# ESP_Guage_PCB_Sch.net
KiCad netlist of a schematic drawn in Altium Designer
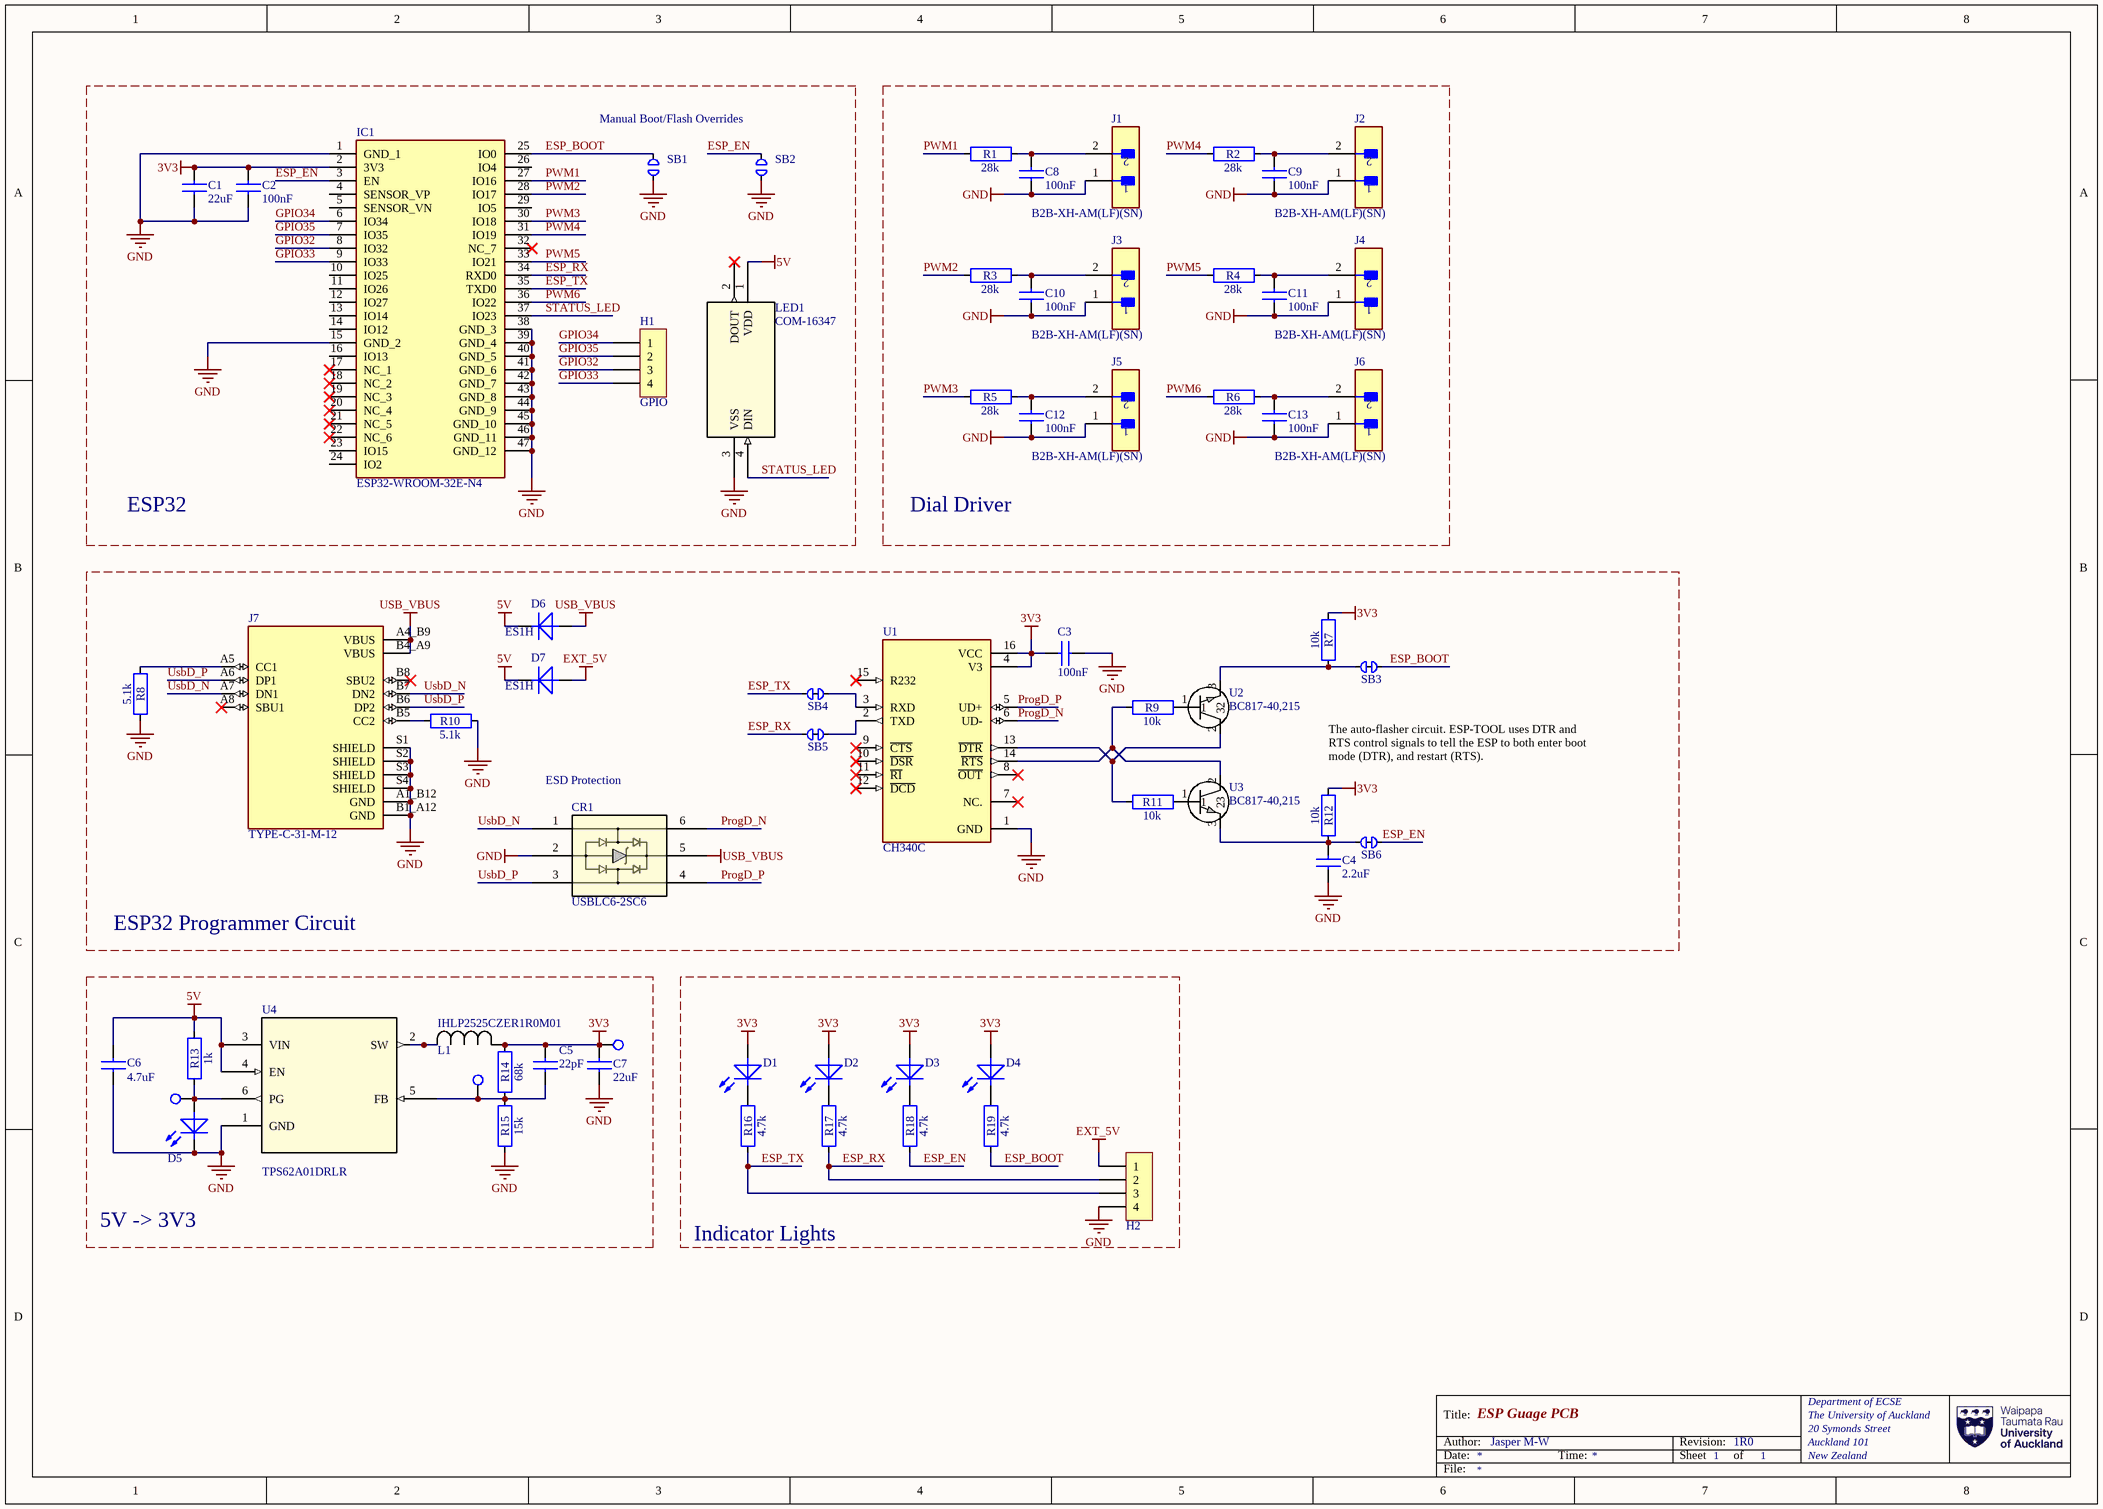
[diagram p0: ESP Guage PCB_Sch.SchDoc]

(export (version "E")
  (design (tool "Eeschema 10.0.6"))
  (components
    (comp (ref "C1")
      (value "22uF")
      (footprint "C0805")
      (description "Generic 0805 cramic capacitor")
      (libsource (lib "UGs@UoA") (part "CCAP0805"))
    )
    (comp (ref "C2")
      (value "100nF")
      (footprint "C0805")
      (description "Generic 0805 cramic capacitor")
      (libsource (lib "UGs@UoA") (part "CCAP0805"))
    )
    (comp (ref "C3")
      (value "100nF")
      (footprint "C0805")
      (description "Generic 0805 cramic capacitor")
      (libsource (lib "UGs@UoA") (part "CCAP0805"))
    )
    (comp (ref "C4")
      (value "2.2uF")
      (footprint "C0805")
      (description "Generic 0805 cramic capacitor")
      (libsource (lib "UGs@UoA") (part "CCAP0805"))
    )
    (comp (ref "C5")
      (value "22pF")
      (footprint "C0805")
      (description "Generic 0805 cramic capacitor")
      (libsource (lib "UGs@UoA") (part "CCAP0805"))
    )
    (comp (ref "C6")
      (value "4.7uF")
      (footprint "C0805")
      (description "Generic 0805 cramic capacitor")
      (libsource (lib "UGs@UoA") (part "CCAP0805"))
    )
    (comp (ref "C7")
      (value "22uF")
      (footprint "C0805")
      (description "Generic 0805 cramic capacitor")
      (libsource (lib "UGs@UoA") (part "CCAP0805"))
    )
    (comp (ref "C8")
      (value "100nF")
      (footprint "C0805")
      (description "Generic 0805 cramic capacitor")
      (libsource (lib "UGs@UoA") (part "CCAP0805"))
    )
    (comp (ref "C9")
      (value "100nF")
      (footprint "C0805")
      (description "Generic 0805 cramic capacitor")
      (libsource (lib "UGs@UoA") (part "CCAP0805"))
    )
    (comp (ref "C10")
      (value "100nF")
      (footprint "C0805")
      (description "Generic 0805 cramic capacitor")
      (libsource (lib "UGs@UoA") (part "CCAP0805"))
    )
    (comp (ref "C11")
      (value "100nF")
      (footprint "C0805")
      (description "Generic 0805 cramic capacitor")
      (libsource (lib "UGs@UoA") (part "CCAP0805"))
    )
    (comp (ref "C12")
      (value "100nF")
      (footprint "C0805")
      (description "Generic 0805 cramic capacitor")
      (libsource (lib "UGs@UoA") (part "CCAP0805"))
    )
    (comp (ref "C13")
      (value "100nF")
      (footprint "C0805")
      (description "Generic 0805 cramic capacitor")
      (libsource (lib "UGs@UoA") (part "CCAP0805"))
    )
    (comp (ref "CR1")
      (value "USBLC6-2SC6")
      (footprint "SOT23-6L_STM")
      (description "ESD Protection for USB 2.0 High Speed")
      (fields (field (name "COPYRIGHT") "Copyright (C) 2025 Ultra Librarian. All rights reserved."))
      (libsource (lib "ESDProtect_USBLC6-2SC6") (part "USBLC6-2SC6"))
    )
    (comp (ref "D1")
      (value "LED_0805")
      (footprint "LED_0805-Footprint-1")
      (description "Generic SMT LED 0805")
      (libsource (lib "UGs@UoA") (part "LED"))
    )
    (comp (ref "D2")
      (value "LED_0805")
      (footprint "LED_0805-Footprint-1")
      (description "Generic SMT LED 0805")
      (libsource (lib "UGs@UoA") (part "LED"))
    )
    (comp (ref "D3")
      (value "LED_0805")
      (footprint "LED_0805-Footprint-1")
      (description "Generic SMT LED 0805")
      (libsource (lib "UGs@UoA") (part "LED"))
    )
    (comp (ref "D4")
      (value "LED_0805")
      (footprint "LED_0805-Footprint-1")
      (description "Generic SMT LED 0805")
      (libsource (lib "UGs@UoA") (part "LED"))
    )
    (comp (ref "D5")
      (value "LED_0805")
      (footprint "LED_0805-Footprint-1")
      (description "Generic SMT LED 0805")
      (libsource (lib "UGs@UoA") (part "LED"))
    )
    (comp (ref "D6")
      (value "ES1H")
      (footprint "DO-214AC")
      (description "Rectifier Diode, 1 Phase, 1 Element, 1A, 500V V(RRM), Silicon, DO-214AC")
      (libsource (lib "UGs@UoA") (part "Diode"))
    )
    (comp (ref "D7")
      (value "ES1H")
      (footprint "DO-214AC")
      (description "Rectifier Diode, 1 Phase, 1 Element, 1A, 500V V(RRM), Silicon, DO-214AC")
      (libsource (lib "UGs@UoA") (part "Diode"))
    )
    (comp (ref "H1")
      (value "GPIO")
      (footprint "HEADER_2.54MM_1x4PIN")
      (description "JTAG")
      (libsource (lib "Generic") (part "1x4 Header 2.54mm"))
    )
    (comp (ref "H2")
      (value "1x4 Header 2.54mm")
      (footprint "HEADER_2.54MM_1x4PIN")
      (libsource (lib "Generic") (part "1x4 Header 2.54mm"))
    )
    (comp (ref "IC1")
      (value "ESP32-WROOM-32E-N4")
      (footprint "ESP32WROOM32EN4")
      (description "RX TXRX MOD WIFI TRACE ANT SMD")
      (fields (field (name "MOUSER PART NUMBER") "356-ESP32WRM32E132PH"))
      (libsource (lib "ESP32-WROOM-32E-N4") (part "ESP32-WROOM-32E-N4"))
    )
    (comp (ref "J1")
      (value "B2B-XH-AM(LF)(SN)")
      (footprint "FP-B2B-XH-AM_LF_SN-MFG")
      (description "CONN HEADER VERT 2POS 2.5MM")
      (libsource (lib "Altium Content Vault") (part "3bc925449376181038e59eaffc5286c"))
    )
    (comp (ref "J2")
      (value "B2B-XH-AM(LF)(SN)")
      (footprint "FP-B2B-XH-AM_LF_SN-MFG")
      (description "CONN HEADER VERT 2POS 2.5MM")
      (libsource (lib "Altium Content Vault") (part "3bc925449376181038e59eaffc5286c"))
    )
    (comp (ref "J3")
      (value "B2B-XH-AM(LF)(SN)")
      (footprint "FP-B2B-XH-AM_LF_SN-MFG")
      (description "CONN HEADER VERT 2POS 2.5MM")
      (libsource (lib "Altium Content Vault") (part "3bc925449376181038e59eaffc5286c"))
    )
    (comp (ref "J4")
      (value "B2B-XH-AM(LF)(SN)")
      (footprint "FP-B2B-XH-AM_LF_SN-MFG")
      (description "CONN HEADER VERT 2POS 2.5MM")
      (libsource (lib "Altium Content Vault") (part "3bc925449376181038e59eaffc5286c"))
    )
    (comp (ref "J5")
      (value "B2B-XH-AM(LF)(SN)")
      (footprint "FP-B2B-XH-AM_LF_SN-MFG")
      (description "CONN HEADER VERT 2POS 2.5MM")
      (libsource (lib "Altium Content Vault") (part "3bc925449376181038e59eaffc5286c"))
    )
    (comp (ref "J6")
      (value "B2B-XH-AM(LF)(SN)")
      (footprint "FP-B2B-XH-AM_LF_SN-MFG")
      (description "CONN HEADER VERT 2POS 2.5MM")
      (libsource (lib "Altium Content Vault") (part "3bc925449376181038e59eaffc5286c"))
    )
    (comp (ref "J7")
      (value "TYPE-C-31-M-12")
      (footprint "HRO_TYPE-C-31-M-12")
      (description "USB Connectors 24 Receptacle 1 8.94*7.3mm RoHS")
      (fields (field (name "MF") "HRO Electronics Co., Ltd."))
      (libsource (lib "UsbFull_TYPE-C-31-M-12") (part "TYPE-C-31-M-12"))
    )
    (comp (ref "L1")
      (value "IHLP2525CZER1R0M01")
      (footprint "IND_IHLP-2525CZ-01_VIS")
      (description "IHLP-2525CZ-01 1 20% ER E3 1uH")
      (fields (field (name "COPYRIGHT") "Copyright (C) 2025 Ultra Librarian. All rights reserved."))
      (libsource (lib "PowerIndcutor_IHLP2525CZER1R0M01") (part "IHLP2525CZER1R0M01"))
    )
    (comp (ref "LED1")
      (value "COM-16347")
      (footprint "COM-16347_SPK")
      (description "Description")
      (fields (field (name "COPYRIGHT") "Copyright (C) 2026 Ultra Librarian. All rights reserved."))
      (libsource (lib "AddrLED_COM-16347") (part "COM-16347"))
    )
    (comp (ref "R1")
      (value "28k")
      (footprint "R0805")
      (description "Generic 0805 resistor")
      (fields (field (name "Comment") "10kj"))
      (libsource (lib "UGs@UoA") (part "RES0805"))
    )
    (comp (ref "R2")
      (value "28k")
      (footprint "R0805")
      (description "Generic 0805 resistor")
      (fields (field (name "Comment") "10kj"))
      (libsource (lib "UGs@UoA") (part "RES0805"))
    )
    (comp (ref "R3")
      (value "28k")
      (footprint "R0805")
      (description "Generic 0805 resistor")
      (fields (field (name "Comment") "10kj"))
      (libsource (lib "UGs@UoA") (part "RES0805"))
    )
    (comp (ref "R4")
      (value "28k")
      (footprint "R0805")
      (description "Generic 0805 resistor")
      (fields (field (name "Comment") "10kj"))
      (libsource (lib "UGs@UoA") (part "RES0805"))
    )
    (comp (ref "R5")
      (value "28k")
      (footprint "R0805")
      (description "Generic 0805 resistor")
      (fields (field (name "Comment") "10kj"))
      (libsource (lib "UGs@UoA") (part "RES0805"))
    )
    (comp (ref "R6")
      (value "28k")
      (footprint "R0805")
      (description "Generic 0805 resistor")
      (fields (field (name "Comment") "10kj"))
      (libsource (lib "UGs@UoA") (part "RES0805"))
    )
    (comp (ref "R7")
      (value "10k")
      (footprint "R0805")
      (description "Generic 0805 resistor")
      (fields (field (name "Comment") "10kj"))
      (libsource (lib "") (part "RES0805_1"))
    )
    (comp (ref "R8")
      (value "5.1k")
      (footprint "R0805")
      (description "Generic 0805 resistor")
      (fields (field (name "Comment") "10kj"))
      (libsource (lib "") (part "RES0805_1"))
    )
    (comp (ref "R9")
      (value "10k")
      (footprint "R0805")
      (description "Generic 0805 resistor")
      (fields (field (name "Comment") "10kj"))
      (libsource (lib "UGs@UoA") (part "RES0805"))
    )
    (comp (ref "R10")
      (value "5.1k")
      (footprint "R0805")
      (description "Generic 0805 resistor")
      (fields (field (name "Comment") "10kj"))
      (libsource (lib "UGs@UoA") (part "RES0805"))
    )
    (comp (ref "R11")
      (value "10k")
      (footprint "R0805")
      (description "Generic 0805 resistor")
      (fields (field (name "Comment") "10kj"))
      (libsource (lib "UGs@UoA") (part "RES0805"))
    )
    (comp (ref "R12")
      (value "10k")
      (footprint "R0805")
      (description "Generic 0805 resistor")
      (fields (field (name "Comment") "10kj"))
      (libsource (lib "") (part "RES0805_1"))
    )
    (comp (ref "R13")
      (value "1k")
      (footprint "R0805")
      (description "Generic 0805 resistor")
      (fields (field (name "Comment") "10kj"))
      (libsource (lib "") (part "RES0805_2"))
    )
    (comp (ref "R14")
      (value "68k")
      (footprint "R0805")
      (description "Generic 0805 resistor")
      (fields (field (name "Comment") "10kj"))
      (libsource (lib "") (part "RES0805_2"))
    )
    (comp (ref "R15")
      (value "15k")
      (footprint "R0805")
      (description "Generic 0805 resistor")
      (fields (field (name "Comment") "10kj"))
      (libsource (lib "") (part "RES0805_2"))
    )
    (comp (ref "R16")
      (value "4.7k")
      (footprint "R0805")
      (description "Generic 0805 resistor")
      (fields (field (name "Comment") "10kj"))
      (libsource (lib "") (part "RES0805_2"))
    )
    (comp (ref "R17")
      (value "4.7k")
      (footprint "R0805")
      (description "Generic 0805 resistor")
      (fields (field (name "Comment") "10kj"))
      (libsource (lib "") (part "RES0805_2"))
    )
    (comp (ref "R18")
      (value "4.7k")
      (footprint "R0805")
      (description "Generic 0805 resistor")
      (fields (field (name "Comment") "10kj"))
      (libsource (lib "") (part "RES0805_2"))
    )
    (comp (ref "R19")
      (value "4.7k")
      (footprint "R0805")
      (description "Generic 0805 resistor")
      (fields (field (name "Comment") "10kj"))
      (libsource (lib "") (part "RES0805_2"))
    )
    (comp (ref "SB1")
      (value "Solder Jumper Normally Open 0201")
      (footprint "Solder Bridge Open 0201")
      (libsource (lib "Generic") (part "Solder Jumper Normally Open 0201"))
    )
    (comp (ref "SB2")
      (value "Solder Jumper Normally Open 0201")
      (footprint "Solder Bridge Open 0201")
      (libsource (lib "Generic") (part "Solder Jumper Normally Open 0201"))
    )
    (comp (ref "SB3")
      (value "Solder Jumper Normally Closed 0201")
      (footprint "Solder Bridge Closed 0201")
      (libsource (lib "Generic") (part "Solder Jumper Normally Closed 0201"))
    )
    (comp (ref "SB4")
      (value "Solder Jumper Normally Closed 0201")
      (footprint "Solder Bridge Closed 0201")
      (libsource (lib "Generic") (part "Solder Jumper Normally Closed 0201"))
    )
    (comp (ref "SB5")
      (value "Solder Jumper Normally Closed 0201")
      (footprint "Solder Bridge Closed 0201")
      (libsource (lib "Generic") (part "Solder Jumper Normally Closed 0201"))
    )
    (comp (ref "SB6")
      (value "Solder Jumper Normally Closed 0201")
      (footprint "Solder Bridge Closed 0201")
      (libsource (lib "Generic") (part "Solder Jumper Normally Closed 0201"))
    )
    (comp (ref "T_5")
      (value "Surface Test Pad")
      (footprint "Test Pad")
      (libsource (lib "Generic") (part "Surface Test Pad"))
    )
    (comp (ref "T_FB1")
      (value "Surface Test Pad")
      (footprint "Test Pad")
      (libsource (lib "Generic") (part "Surface Test Pad"))
    )
    (comp (ref "T_PROG1")
      (value "Surface Test Pad")
      (footprint "Test Pad")
      (libsource (lib "Generic") (part "Surface Test Pad"))
    )
    (comp (ref "U1")
      (value "CH340C")
      (footprint "SOIC127P600X180-16N")
      (description "USB to serial chip CH340")
      (fields (field (name "MF") "WCH"))
      (libsource (lib "CH340C") (part "CH340C"))
    )
    (comp (ref "U2")
      (value "BC817-40,215")
      (footprint "SOT23_NEX")
      (description "Description")
      (fields (field (name "COPYRIGHT") "Copyright (C) 2026 Ultra Librarian. All rights reserved."))
      (libsource (lib "NPNTransistor_BC817-40,215") (part "BC817-40,215"))
    )
    (comp (ref "U3")
      (value "BC817-40,215")
      (footprint "SOT23_NEX")
      (description "Description")
      (fields (field (name "COPYRIGHT") "Copyright (C) 2026 Ultra Librarian. All rights reserved."))
      (libsource (lib "NPNTransistor_BC817-40,215") (part "BC817-40,215"))
    )
    (comp (ref "U4")
      (value "TPS62A01DRLR")
      (footprint "SOT6_DRL_TEX")
      (description "2.5V-to-5.5V input, 1A output high-efficiency step-down converter 6-SOT-5X3 -40 to 125")
      (fields (field (name "COPYRIGHT") "Copyright (C) 2025 Ultra Librarian. All rights reserved."))
      (libsource (lib "BuckReg_TPS62A01DRLR") (part "TPS62A01DRLR"))
    )
  )
  (nets
    (net (code "1") (name "/ESP_BOOT") (class "Default")
      (node (ref "IC1") (pin "25") (pinfunction "IO0_25") (pintype "passive"))
      (node (ref "R19") (pin "1") (pinfunction "1_1") (pintype "passive"))
      (node (ref "SB1") (pin "2") (pinfunction "2_2") (pintype "passive"))
      (node (ref "SB3") (pin "1") (pinfunction "1_1") (pintype "passive"))
    )
    (net (code "2") (name "/ESP_EN") (class "Default")
      (node (ref "IC1") (pin "3") (pinfunction "EN_3") (pintype "passive"))
      (node (ref "R18") (pin "1") (pinfunction "1_1") (pintype "passive"))
      (node (ref "SB2") (pin "2") (pinfunction "2_2") (pintype "passive"))
      (node (ref "SB6") (pin "1") (pinfunction "1_1") (pintype "passive"))
    )
    (net (code "3") (name "/ESP_RX") (class "Default")
      (node (ref "H2") (pin "2") (pinfunction "2_2") (pintype "passive"))
      (node (ref "IC1") (pin "34") (pinfunction "RXD0_34") (pintype "passive"))
      (node (ref "R17") (pin "1") (pinfunction "1_1") (pintype "passive"))
      (node (ref "SB5") (pin "2") (pinfunction "2_2") (pintype "passive"))
    )
    (net (code "4") (name "/ESP_TX") (class "Default")
      (node (ref "H2") (pin "3") (pinfunction "3_3") (pintype "passive"))
      (node (ref "IC1") (pin "35") (pinfunction "TXD0_35") (pintype "passive"))
      (node (ref "R16") (pin "1") (pinfunction "1_1") (pintype "passive"))
      (node (ref "SB4") (pin "2") (pinfunction "2_2") (pintype "passive"))
    )
    (net (code "5") (name "/GPIO32") (class "Default")
      (node (ref "H1") (pin "3") (pinfunction "3_3") (pintype "passive"))
      (node (ref "IC1") (pin "8") (pinfunction "IO32_8") (pintype "passive"))
    )
    (net (code "6") (name "/GPIO33") (class "Default")
      (node (ref "H1") (pin "4") (pinfunction "4_4") (pintype "passive"))
      (node (ref "IC1") (pin "9") (pinfunction "IO33_9") (pintype "passive"))
    )
    (net (code "7") (name "/GPIO34") (class "Default")
      (node (ref "H1") (pin "1") (pinfunction "1_1") (pintype "passive"))
      (node (ref "IC1") (pin "6") (pinfunction "IO34_6") (pintype "passive"))
    )
    (net (code "8") (name "/GPIO35") (class "Default")
      (node (ref "H1") (pin "2") (pinfunction "2_2") (pintype "passive"))
      (node (ref "IC1") (pin "7") (pinfunction "IO35_7") (pintype "passive"))
    )
    (net (code "9") (name "/PWM1") (class "Default")
      (node (ref "IC1") (pin "27") (pinfunction "IO16_27") (pintype "passive"))
      (node (ref "R1") (pin "1") (pinfunction "1_1") (pintype "passive"))
    )
    (net (code "10") (name "/PWM2") (class "Default")
      (node (ref "IC1") (pin "28") (pinfunction "IO17_28") (pintype "passive"))
      (node (ref "R3") (pin "1") (pinfunction "1_1") (pintype "passive"))
    )
    (net (code "11") (name "/PWM3") (class "Default")
      (node (ref "IC1") (pin "30") (pinfunction "IO18_30") (pintype "passive"))
      (node (ref "R5") (pin "1") (pinfunction "1_1") (pintype "passive"))
    )
    (net (code "12") (name "/PWM4") (class "Default")
      (node (ref "IC1") (pin "31") (pinfunction "IO19_31") (pintype "passive"))
      (node (ref "R2") (pin "1") (pinfunction "1_1") (pintype "passive"))
    )
    (net (code "13") (name "/PWM5") (class "Default")
      (node (ref "IC1") (pin "33") (pinfunction "IO21_33") (pintype "passive"))
      (node (ref "R4") (pin "1") (pinfunction "1_1") (pintype "passive"))
    )
    (net (code "14") (name "/PWM6") (class "Default")
      (node (ref "IC1") (pin "36") (pinfunction "IO22_36") (pintype "passive"))
      (node (ref "R6") (pin "1") (pinfunction "1_1") (pintype "passive"))
    )
    (net (code "15") (name "/ProgD_N") (class "Default")
      (node (ref "CR1") (pin "6") (pinfunction "6_6") (pintype "passive"))
      (node (ref "U1") (pin "6") (pinfunction "UD-_6") (pintype "bidirectional"))
    )
    (net (code "16") (name "/ProgD_P") (class "Default")
      (node (ref "CR1") (pin "4") (pinfunction "4_4") (pintype "passive"))
      (node (ref "U1") (pin "5") (pinfunction "UD+_5") (pintype "bidirectional"))
    )
    (net (code "17") (name "/STATUS_LED") (class "Default")
      (node (ref "IC1") (pin "37") (pinfunction "IO23_37") (pintype "passive"))
      (node (ref "LED1") (pin "4") (pinfunction "DIN_4") (pintype "input"))
    )
    (net (code "18") (name "/UsbD_N") (class "Default")
      (node (ref "CR1") (pin "1") (pinfunction "1_1") (pintype "passive"))
      (node (ref "J7") (pin "A7") (pinfunction "DN1_A7") (pintype "bidirectional"))
      (node (ref "J7") (pin "B7") (pinfunction "DN2_B7") (pintype "bidirectional"))
    )
    (net (code "19") (name "/UsbD_P") (class "Default")
      (node (ref "CR1") (pin "3") (pinfunction "3_3") (pintype "passive"))
      (node (ref "J7") (pin "A6") (pinfunction "DP1_A6") (pintype "bidirectional"))
      (node (ref "J7") (pin "B6") (pinfunction "DP2_B6") (pintype "bidirectional"))
    )
    (net (code "20") (name "3V3") (class "Default")
      (node (ref "C1") (pin "2") (pinfunction "2_2") (pintype "passive"))
      (node (ref "C2") (pin "2") (pinfunction "2_2") (pintype "passive"))
      (node (ref "C3") (pin "2") (pinfunction "2_2") (pintype "passive"))
      (node (ref "C5") (pin "2") (pinfunction "2_2") (pintype "passive"))
      (node (ref "C7") (pin "2") (pinfunction "2_2") (pintype "passive"))
      (node (ref "D1") (pin "2") (pinfunction "A_2") (pintype "passive"))
      (node (ref "D2") (pin "2") (pinfunction "A_2") (pintype "passive"))
      (node (ref "D3") (pin "2") (pinfunction "A_2") (pintype "passive"))
      (node (ref "D4") (pin "2") (pinfunction "A_2") (pintype "passive"))
      (node (ref "IC1") (pin "2") (pinfunction "3V3_2") (pintype "passive"))
      (node (ref "L1") (pin "2") (pinfunction "2_2") (pintype "passive"))
      (node (ref "R12") (pin "1") (pinfunction "1_1") (pintype "passive"))
      (node (ref "R14") (pin "2") (pinfunction "2_2") (pintype "passive"))
      (node (ref "R7") (pin "1") (pinfunction "1_1") (pintype "passive"))
      (node (ref "T_5") (pin "1") (pinfunction "0_1") (pintype "passive"))
      (node (ref "U1") (pin "16") (pinfunction "VCC_16") (pintype "power_in"))
      (node (ref "U1") (pin "4") (pinfunction "V3_4") (pintype "power_in"))
    )
    (net (code "21") (name "5V") (class "Default")
      (node (ref "C6") (pin "2") (pinfunction "2_2") (pintype "passive"))
      (node (ref "D6") (pin "1") (pinfunction "K_1") (pintype "passive"))
      (node (ref "D7") (pin "1") (pinfunction "K_1") (pintype "passive"))
      (node (ref "LED1") (pin "1") (pinfunction "VDD_1") (pintype "power_in"))
      (node (ref "R13") (pin "2") (pinfunction "2_2") (pintype "passive"))
      (node (ref "U4") (pin "3") (pinfunction "VIN_3") (pintype "power_in"))
      (node (ref "U4") (pin "4") (pinfunction "EN_4") (pintype "input"))
    )
    (net (code "22") (name "EXT_5V") (class "Default")
      (node (ref "D7") (pin "2") (pinfunction "A_2") (pintype "passive"))
      (node (ref "H2") (pin "1") (pinfunction "1_1") (pintype "passive"))
    )
    (net (code "23") (name "GND") (class "Default")
      (node (ref "C1") (pin "1") (pinfunction "1_1") (pintype "passive"))
      (node (ref "C10") (pin "2") (pinfunction "2_2") (pintype "passive"))
      (node (ref "C11") (pin "2") (pinfunction "2_2") (pintype "passive"))
      (node (ref "C12") (pin "2") (pinfunction "2_2") (pintype "passive"))
      (node (ref "C13") (pin "2") (pinfunction "2_2") (pintype "passive"))
      (node (ref "C2") (pin "1") (pinfunction "1_1") (pintype "passive"))
      (node (ref "C3") (pin "1") (pinfunction "1_1") (pintype "passive"))
      (node (ref "C4") (pin "1") (pinfunction "1_1") (pintype "passive"))
      (node (ref "C6") (pin "1") (pinfunction "1_1") (pintype "passive"))
      (node (ref "C7") (pin "1") (pinfunction "1_1") (pintype "passive"))
      (node (ref "C8") (pin "2") (pinfunction "2_2") (pintype "passive"))
      (node (ref "C9") (pin "2") (pinfunction "2_2") (pintype "passive"))
      (node (ref "CR1") (pin "2") (pinfunction "2_2") (pintype "passive"))
      (node (ref "D5") (pin "1") (pinfunction "K_1") (pintype "passive"))
      (node (ref "H2") (pin "4") (pinfunction "4_4") (pintype "passive"))
      (node (ref "IC1") (pin "1") (pinfunction "GND_1_1") (pintype "passive"))
      (node (ref "IC1") (pin "15") (pinfunction "GND_2_15") (pintype "passive"))
      (node (ref "IC1") (pin "38") (pinfunction "GND_3_38") (pintype "passive"))
      (node (ref "IC1") (pin "39") (pinfunction "GND_4_39") (pintype "passive"))
      (node (ref "IC1") (pin "40") (pinfunction "GND_5_40") (pintype "passive"))
      (node (ref "IC1") (pin "41") (pinfunction "GND_6_41") (pintype "passive"))
      (node (ref "IC1") (pin "42") (pinfunction "GND_7_42") (pintype "passive"))
      (node (ref "IC1") (pin "43") (pinfunction "GND_8_43") (pintype "passive"))
      (node (ref "IC1") (pin "44") (pinfunction "GND_9_44") (pintype "passive"))
      (node (ref "IC1") (pin "45") (pinfunction "GND_10_45") (pintype "passive"))
      (node (ref "IC1") (pin "46") (pinfunction "GND_11_46") (pintype "passive"))
      (node (ref "IC1") (pin "47") (pinfunction "GND_12_47") (pintype "passive"))
      (node (ref "J1") (pin "1") (pinfunction "1_1") (pintype "passive"))
      (node (ref "J2") (pin "1") (pinfunction "1_1") (pintype "passive"))
      (node (ref "J3") (pin "1") (pinfunction "1_1") (pintype "passive"))
      (node (ref "J4") (pin "1") (pinfunction "1_1") (pintype "passive"))
      (node (ref "J5") (pin "1") (pinfunction "1_1") (pintype "passive"))
      (node (ref "J6") (pin "1") (pinfunction "1_1") (pintype "passive"))
      (node (ref "J7") (pin "A1_B12") (pinfunction "GND_A1_B12") (pintype "power_in"))
      (node (ref "J7") (pin "B1_A12") (pinfunction "GND_B1_A12") (pintype "power_in"))
      (node (ref "J7") (pin "S1") (pinfunction "SHIELD_S1") (pintype "passive"))
      (node (ref "J7") (pin "S2") (pinfunction "SHIELD_S2") (pintype "passive"))
      (node (ref "J7") (pin "S3") (pinfunction "SHIELD_S3") (pintype "passive"))
      (node (ref "J7") (pin "S4") (pinfunction "SHIELD_S4") (pintype "passive"))
      (node (ref "LED1") (pin "3") (pinfunction "VSS_3") (pintype "power_in"))
      (node (ref "R10") (pin "2") (pinfunction "2_2") (pintype "passive"))
      (node (ref "R15") (pin "1") (pinfunction "1_1") (pintype "passive"))
      (node (ref "R8") (pin "2") (pinfunction "2_2") (pintype "passive"))
      (node (ref "SB1") (pin "1") (pinfunction "1_1") (pintype "passive"))
      (node (ref "SB2") (pin "1") (pinfunction "1_1") (pintype "passive"))
      (node (ref "U1") (pin "1") (pinfunction "GND_1") (pintype "power_in"))
      (node (ref "U4") (pin "1") (pinfunction "GND_1") (pintype "power_in"))
    )
    (net (code "24") (name "Net-(C8-Pad1)") (class "Default")
      (node (ref "C8") (pin "1") (pinfunction "1_1") (pintype "passive"))
      (node (ref "J1") (pin "2") (pinfunction "2_2") (pintype "passive"))
      (node (ref "R1") (pin "2") (pinfunction "2_2") (pintype "passive"))
    )
    (net (code "25") (name "Net-(C9-Pad1)") (class "Default")
      (node (ref "C9") (pin "1") (pinfunction "1_1") (pintype "passive"))
      (node (ref "J2") (pin "2") (pinfunction "2_2") (pintype "passive"))
      (node (ref "R2") (pin "2") (pinfunction "2_2") (pintype "passive"))
    )
    (net (code "26") (name "Net-(C10-Pad1)") (class "Default")
      (node (ref "C10") (pin "1") (pinfunction "1_1") (pintype "passive"))
      (node (ref "J3") (pin "2") (pinfunction "2_2") (pintype "passive"))
      (node (ref "R3") (pin "2") (pinfunction "2_2") (pintype "passive"))
    )
    (net (code "27") (name "Net-(C11-Pad1)") (class "Default")
      (node (ref "C11") (pin "1") (pinfunction "1_1") (pintype "passive"))
      (node (ref "J4") (pin "2") (pinfunction "2_2") (pintype "passive"))
      (node (ref "R4") (pin "2") (pinfunction "2_2") (pintype "passive"))
    )
    (net (code "28") (name "Net-(C12-Pad1)") (class "Default")
      (node (ref "C12") (pin "1") (pinfunction "1_1") (pintype "passive"))
      (node (ref "J5") (pin "2") (pinfunction "2_2") (pintype "passive"))
      (node (ref "R5") (pin "2") (pinfunction "2_2") (pintype "passive"))
    )
    (net (code "29") (name "Net-(C13-Pad1)") (class "Default")
      (node (ref "C13") (pin "1") (pinfunction "1_1") (pintype "passive"))
      (node (ref "J6") (pin "2") (pinfunction "2_2") (pintype "passive"))
      (node (ref "R6") (pin "2") (pinfunction "2_2") (pintype "passive"))
    )
    (net (code "30") (name "Net-(D1-K)") (class "Default")
      (node (ref "D1") (pin "1") (pinfunction "K_1") (pintype "passive"))
      (node (ref "R16") (pin "2") (pinfunction "2_2") (pintype "passive"))
    )
    (net (code "31") (name "Net-(D2-K)") (class "Default")
      (node (ref "D2") (pin "1") (pinfunction "K_1") (pintype "passive"))
      (node (ref "R17") (pin "2") (pinfunction "2_2") (pintype "passive"))
    )
    (net (code "32") (name "Net-(D3-K)") (class "Default")
      (node (ref "D3") (pin "1") (pinfunction "K_1") (pintype "passive"))
      (node (ref "R18") (pin "2") (pinfunction "2_2") (pintype "passive"))
    )
    (net (code "33") (name "Net-(D4-K)") (class "Default")
      (node (ref "D4") (pin "1") (pinfunction "K_1") (pintype "passive"))
      (node (ref "R19") (pin "2") (pinfunction "2_2") (pintype "passive"))
    )
    (net (code "34") (name "Net-(D5-A)") (class "Default")
      (node (ref "D5") (pin "2") (pinfunction "A_2") (pintype "passive"))
      (node (ref "R13") (pin "1") (pinfunction "1_1") (pintype "passive"))
      (node (ref "T_PROG1") (pin "1") (pinfunction "0_1") (pintype "passive"))
      (node (ref "U4") (pin "6") (pinfunction "PG_6") (pintype "output"))
    )
    (net (code "35") (name "Net-(J7-CC1)") (class "Default")
      (node (ref "J7") (pin "A5") (pinfunction "CC1_A5") (pintype "bidirectional"))
      (node (ref "R8") (pin "1") (pinfunction "1_1") (pintype "passive"))
    )
    (net (code "36") (name "Net-(J7-CC2)") (class "Default")
      (node (ref "J7") (pin "B5") (pinfunction "CC2_B5") (pintype "bidirectional"))
      (node (ref "R10") (pin "1") (pinfunction "1_1") (pintype "passive"))
    )
    (net (code "37") (name "Net-(R9-Pad2)") (class "Default")
      (node (ref "R9") (pin "2") (pinfunction "2_2") (pintype "passive"))
      (node (ref "U2") (pin "1") (pinfunction "1_1") (pintype "passive"))
    )
    (net (code "38") (name "Net-(R11-Pad2)") (class "Default")
      (node (ref "R11") (pin "2") (pinfunction "2_2") (pintype "passive"))
      (node (ref "U3") (pin "1") (pinfunction "1_1") (pintype "passive"))
    )
    (net (code "39") (name "Net-(T_FB1-0)") (class "Default")
      (node (ref "C5") (pin "1") (pinfunction "1_1") (pintype "passive"))
      (node (ref "R14") (pin "1") (pinfunction "1_1") (pintype "passive"))
      (node (ref "R15") (pin "2") (pinfunction "2_2") (pintype "passive"))
      (node (ref "T_FB1") (pin "1") (pinfunction "0_1") (pintype "passive"))
      (node (ref "U4") (pin "5") (pinfunction "FB_5") (pintype "input"))
    )
    (net (code "40") (name "Net-(U1-RXD)") (class "Default")
      (node (ref "SB4") (pin "1") (pinfunction "1_1") (pintype "passive"))
      (node (ref "U1") (pin "3") (pinfunction "RXD_3") (pintype "input"))
    )
    (net (code "41") (name "Net-(U1-TXD)") (class "Default")
      (node (ref "SB5") (pin "1") (pinfunction "1_1") (pintype "passive"))
      (node (ref "U1") (pin "2") (pinfunction "TXD_2") (pintype "output"))
    )
    (net (code "42") (name "Net-(U1-~{DTR})") (class "Default")
      (node (ref "R11") (pin "1") (pinfunction "1_1") (pintype "passive"))
      (node (ref "U1") (pin "13") (pinfunction "~{DTR}_13") (pintype "output"))
      (node (ref "U2") (pin "2") (pinfunction "3_2") (pintype "passive"))
    )
    (net (code "43") (name "Net-(U1-~{RTS})") (class "Default")
      (node (ref "R9") (pin "1") (pinfunction "1_1") (pintype "passive"))
      (node (ref "U1") (pin "14") (pinfunction "~{RTS}_14") (pintype "output"))
      (node (ref "U3") (pin "2") (pinfunction "3_2") (pintype "passive"))
    )
    (net (code "44") (name "Net-(U2-2)") (class "Default")
      (node (ref "R7") (pin "2") (pinfunction "2_2") (pintype "passive"))
      (node (ref "SB3") (pin "2") (pinfunction "2_2") (pintype "passive"))
      (node (ref "U2") (pin "3") (pinfunction "2_3") (pintype "passive"))
    )
    (net (code "45") (name "Net-(U3-2)") (class "Default")
      (node (ref "C4") (pin "2") (pinfunction "2_2") (pintype "passive"))
      (node (ref "R12") (pin "2") (pinfunction "2_2") (pintype "passive"))
      (node (ref "SB6") (pin "2") (pinfunction "2_2") (pintype "passive"))
      (node (ref "U3") (pin "3") (pinfunction "2_3") (pintype "passive"))
    )
    (net (code "46") (name "Net-(U4-SW)") (class "Default")
      (node (ref "L1") (pin "1") (pinfunction "1_1") (pintype "passive"))
      (node (ref "U4") (pin "2") (pinfunction "SW_2") (pintype "output"))
    )
    (net (code "47") (name "USB_VBUS") (class "Default")
      (node (ref "CR1") (pin "5") (pinfunction "5_5") (pintype "passive"))
      (node (ref "D6") (pin "2") (pinfunction "A_2") (pintype "passive"))
      (node (ref "J7") (pin "A4_B9") (pinfunction "VBUS_A4_B9") (pintype "power_in"))
      (node (ref "J7") (pin "B4_A9") (pinfunction "VBUS_B4_A9") (pintype "power_in"))
    )
    (net (code "48") (name "unconnected-(IC1-IO2-Pad24)") (class "Default")
      (node (ref "IC1") (pin "24") (pinfunction "IO2_24") (pintype "passive"))
    )
    (net (code "49") (name "unconnected-(IC1-IO4-Pad26)") (class "Default")
      (node (ref "IC1") (pin "26") (pinfunction "IO4_26") (pintype "passive"))
    )
    (net (code "50") (name "unconnected-(IC1-IO5-Pad29)") (class "Default")
      (node (ref "IC1") (pin "29") (pinfunction "IO5_29") (pintype "passive"))
    )
    (net (code "51") (name "unconnected-(IC1-IO12-Pad14)") (class "Default")
      (node (ref "IC1") (pin "14") (pinfunction "IO12_14") (pintype "passive"))
    )
    (net (code "52") (name "unconnected-(IC1-IO13-Pad16)") (class "Default")
      (node (ref "IC1") (pin "16") (pinfunction "IO13_16") (pintype "passive"))
    )
    (net (code "53") (name "unconnected-(IC1-IO14-Pad13)") (class "Default")
      (node (ref "IC1") (pin "13") (pinfunction "IO14_13") (pintype "passive"))
    )
    (net (code "54") (name "unconnected-(IC1-IO15-Pad23)") (class "Default")
      (node (ref "IC1") (pin "23") (pinfunction "IO15_23") (pintype "passive"))
    )
    (net (code "55") (name "unconnected-(IC1-IO25-Pad10)") (class "Default")
      (node (ref "IC1") (pin "10") (pinfunction "IO25_10") (pintype "passive"))
    )
    (net (code "56") (name "unconnected-(IC1-IO26-Pad11)") (class "Default")
      (node (ref "IC1") (pin "11") (pinfunction "IO26_11") (pintype "passive"))
    )
    (net (code "57") (name "unconnected-(IC1-IO27-Pad12)") (class "Default")
      (node (ref "IC1") (pin "12") (pinfunction "IO27_12") (pintype "passive"))
    )
    (net (code "58") (name "unconnected-(IC1-NC_1-Pad17)") (class "Default")
      (node (ref "IC1") (pin "17") (pinfunction "NC_1_17") (pintype "passive+no_connect"))
    )
    (net (code "59") (name "unconnected-(IC1-NC_2-Pad18)") (class "Default")
      (node (ref "IC1") (pin "18") (pinfunction "NC_2_18") (pintype "passive+no_connect"))
    )
    (net (code "60") (name "unconnected-(IC1-NC_3-Pad19)") (class "Default")
      (node (ref "IC1") (pin "19") (pinfunction "NC_3_19") (pintype "passive+no_connect"))
    )
    (net (code "61") (name "unconnected-(IC1-NC_4-Pad20)") (class "Default")
      (node (ref "IC1") (pin "20") (pinfunction "NC_4_20") (pintype "passive+no_connect"))
    )
    (net (code "62") (name "unconnected-(IC1-NC_5-Pad21)") (class "Default")
      (node (ref "IC1") (pin "21") (pinfunction "NC_5_21") (pintype "passive+no_connect"))
    )
    (net (code "63") (name "unconnected-(IC1-NC_6-Pad22)") (class "Default")
      (node (ref "IC1") (pin "22") (pinfunction "NC_6_22") (pintype "passive+no_connect"))
    )
    (net (code "64") (name "unconnected-(IC1-NC_7-Pad32)") (class "Default")
      (node (ref "IC1") (pin "32") (pinfunction "NC_7_32") (pintype "passive+no_connect"))
    )
    (net (code "65") (name "unconnected-(IC1-SENSOR_VN-Pad5)") (class "Default")
      (node (ref "IC1") (pin "5") (pinfunction "SENSOR_VN_5") (pintype "passive"))
    )
    (net (code "66") (name "unconnected-(IC1-SENSOR_VP-Pad4)") (class "Default")
      (node (ref "IC1") (pin "4") (pinfunction "SENSOR_VP_4") (pintype "passive"))
    )
    (net (code "67") (name "unconnected-(J7-SBU1-PadA8)") (class "Default")
      (node (ref "J7") (pin "A8") (pinfunction "SBU1_A8") (pintype "bidirectional+no_connect"))
    )
    (net (code "68") (name "unconnected-(J7-SBU2-PadB8)") (class "Default")
      (node (ref "J7") (pin "B8") (pinfunction "SBU2_B8") (pintype "bidirectional+no_connect"))
    )
    (net (code "69") (name "unconnected-(LED1-DOUT-Pad2)") (class "Default")
      (node (ref "LED1") (pin "2") (pinfunction "DOUT_2") (pintype "output+no_connect"))
    )
    (net (code "70") (name "unconnected-(U1-NC.-Pad7)") (class "Default")
      (node (ref "U1") (pin "7") (pinfunction "NC._7") (pintype "passive+no_connect"))
    )
    (net (code "71") (name "unconnected-(U1-R232-Pad15)") (class "Default")
      (node (ref "U1") (pin "15") (pinfunction "R232_15") (pintype "input+no_connect"))
    )
    (net (code "72") (name "unconnected-(U1-~{CTS}-Pad9)") (class "Default")
      (node (ref "U1") (pin "9") (pinfunction "~{CTS}_9") (pintype "input+no_connect"))
    )
    (net (code "73") (name "unconnected-(U1-~{DCD}-Pad12)") (class "Default")
      (node (ref "U1") (pin "12") (pinfunction "~{DCD}_12") (pintype "input+no_connect"))
    )
    (net (code "74") (name "unconnected-(U1-~{DSR}-Pad10)") (class "Default")
      (node (ref "U1") (pin "10") (pinfunction "~{DSR}_10") (pintype "input+no_connect"))
    )
    (net (code "75") (name "unconnected-(U1-~{OUT}-Pad8)") (class "Default")
      (node (ref "U1") (pin "8") (pinfunction "~{OUT}_8") (pintype "output+no_connect"))
    )
    (net (code "76") (name "unconnected-(U1-~{RI}-Pad11)") (class "Default")
      (node (ref "U1") (pin "11") (pinfunction "~{RI}_11") (pintype "input+no_connect"))
    )
  )
)
